# Adafruit_APDS9960_Proximity_Sensor.net
KiCad netlist of a schematic drawn in EAGLE
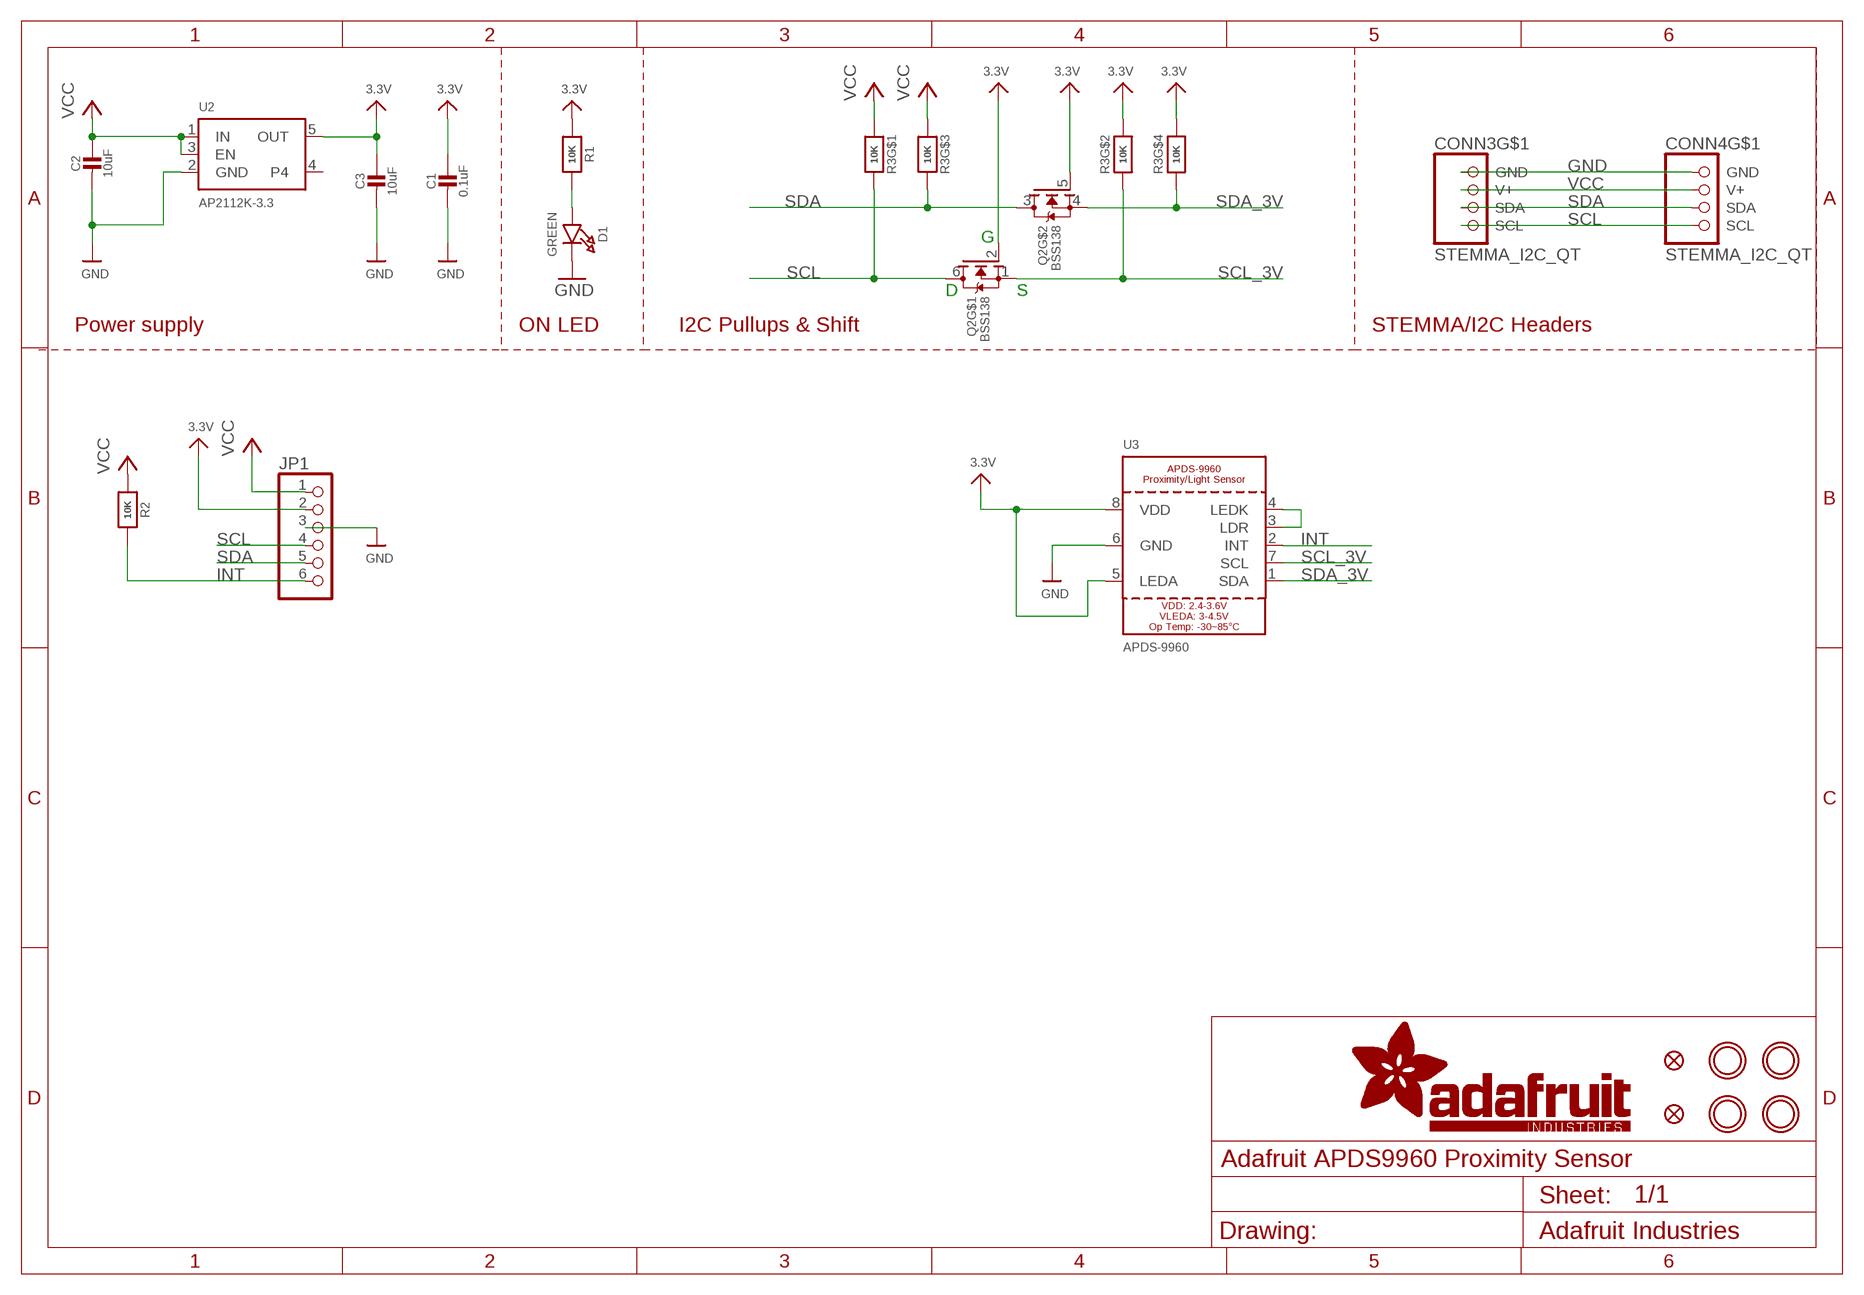
[diagram p0: schematic, sheet 1]

(export (version "E")
  (design (tool "Eeschema 10.0.6"))
  (components
    (comp (ref "C1")
      (value "0.1uF")
      (footprint "eagle-import:0603-NO")
      (libsource (lib "eagle-import") (part "CAP_CERAMIC0603_NO"))
    )
    (comp (ref "C2")
      (value "10uF")
      (footprint "eagle-import:0805-NO")
      (libsource (lib "eagle-import") (part "CAP_CERAMIC0805-NOOUTLINE"))
    )
    (comp (ref "C3")
      (value "10uF")
      (footprint "eagle-import:0805-NO")
      (libsource (lib "eagle-import") (part "CAP_CERAMIC0805-NOOUTLINE"))
    )
    (comp (ref "CONN3")
      (value "STEMMA_I2C_QT")
      (footprint "eagle-import:JST_SH4")
      (libsource (lib "eagle-import") (part "STEMMA_I2C_QT"))
    )
    (comp (ref "CONN4")
      (value "STEMMA_I2C_QT")
      (footprint "eagle-import:JST_SH4")
      (libsource (lib "eagle-import") (part "STEMMA_I2C_QT"))
    )
    (comp (ref "D1")
      (value "GREEN")
      (footprint "eagle-import:CHIPLED_0603_NOOUTLINE")
      (libsource (lib "eagle-import") (part "LED0603_NOOUTLINE"))
    )
    (comp (ref "FID3")
      (value "FIDUCIAL_1MM")
      (footprint "eagle-import:FIDUCIAL_1MM")
      (libsource (lib "eagle-import") (part "FIDUCIAL_1MM"))
    )
    (comp (ref "FID4")
      (value "FIDUCIAL_1MM")
      (footprint "eagle-import:FIDUCIAL_1MM")
      (libsource (lib "eagle-import") (part "FIDUCIAL_1MM"))
    )
    (comp (ref "JP1")
      (value "HEADER-1X670MIL")
      (footprint "eagle-import:1X06_ROUND_70")
      (libsource (lib "eagle-import") (part "HEADER-1X670MIL"))
    )
    (comp (ref "Q2")
      (value "BSS138")
      (footprint "eagle-import:SOT363")
      (libsource (lib "eagle-import") (part "MOSFET-N_DUAL"))
    )
    (comp (ref "R1")
      (value "10K")
      (footprint "eagle-import:0603-NO")
      (libsource (lib "eagle-import") (part "RESISTOR_0603_NOOUT"))
    )
    (comp (ref "R2")
      (value "10K")
      (footprint "eagle-import:0603-NO")
      (libsource (lib "eagle-import") (part "RESISTOR_0603_NOOUT"))
    )
    (comp (ref "R3")
      (value "10K")
      (footprint "eagle-import:RESPACK_4X0603")
      (libsource (lib "eagle-import") (part "RESISTOR_4PACK"))
    )
    (comp (ref "U$1")
      (value "MOUNTINGHOLE2.5")
      (footprint "eagle-import:MOUNTINGHOLE_2.5_PLATED")
      (libsource (lib "eagle-import") (part "MOUNTINGHOLE2.5"))
    )
    (comp (ref "U$17")
      (value "MOUNTINGHOLE2.5")
      (footprint "eagle-import:MOUNTINGHOLE_2.5_PLATED")
      (libsource (lib "eagle-import") (part "MOUNTINGHOLE2.5"))
    )
    (comp (ref "U$19")
      (value "MOUNTINGHOLE2.5")
      (footprint "eagle-import:MOUNTINGHOLE_2.5_PLATED")
      (libsource (lib "eagle-import") (part "MOUNTINGHOLE2.5"))
    )
    (comp (ref "U$21")
      (value "MOUNTINGHOLE2.5")
      (footprint "eagle-import:MOUNTINGHOLE_2.5_PLATED")
      (libsource (lib "eagle-import") (part "MOUNTINGHOLE2.5"))
    )
    (comp (ref "U2")
      (value "AP2112K-3.3")
      (footprint "eagle-import:SOT23-5")
      (libsource (lib "eagle-import") (part "VREG_SOT23-5"))
    )
    (comp (ref "U3")
      (value "APDS-9960")
      (footprint "eagle-import:APDS-9960")
      (libsource (lib "eagle-import") (part "APDS-9960"))
    )
  )
  (nets
    (net (code "1") (name "/INT") (class "Default")
      (node (ref "JP1") (pin "6") (pinfunction "6_6") (pintype "passive"))
      (node (ref "R2") (pin "2") (pinfunction "2_2") (pintype "passive"))
      (node (ref "U3") (pin "2") (pinfunction "INT_2") (pintype "output"))
    )
    (net (code "2") (name "/SCL") (class "Default")
      (node (ref "CONN3") (pin "4") (pinfunction "SCL_4") (pintype "passive"))
      (node (ref "CONN4") (pin "4") (pinfunction "SCL_4") (pintype "passive"))
      (node (ref "JP1") (pin "4") (pinfunction "4_4") (pintype "passive"))
      (node (ref "Q2") (pin "6") (pinfunction "D_6") (pintype "bidirectional"))
      (node (ref "R3") (pin "8") (pinfunction "2_8") (pintype "passive"))
    )
    (net (code "3") (name "/SCL_3V") (class "Default")
      (node (ref "Q2") (pin "1") (pinfunction "S_1") (pintype "bidirectional"))
      (node (ref "R3") (pin "7") (pinfunction "2_7") (pintype "passive"))
      (node (ref "U3") (pin "7") (pinfunction "SCL_7") (pintype "input"))
    )
    (net (code "4") (name "/SDA") (class "Default")
      (node (ref "CONN3") (pin "3") (pinfunction "SDA_3") (pintype "passive"))
      (node (ref "CONN4") (pin "3") (pinfunction "SDA_3") (pintype "passive"))
      (node (ref "JP1") (pin "5") (pinfunction "5_5") (pintype "passive"))
      (node (ref "Q2") (pin "3") (pinfunction "D_3") (pintype "bidirectional"))
      (node (ref "R3") (pin "6") (pinfunction "2_6") (pintype "passive"))
    )
    (net (code "5") (name "/SDA_3V") (class "Default")
      (node (ref "Q2") (pin "4") (pinfunction "S_4") (pintype "bidirectional"))
      (node (ref "R3") (pin "5") (pinfunction "2_5") (pintype "passive"))
      (node (ref "U3") (pin "1") (pinfunction "SDA_1") (pintype "bidirectional"))
    )
    (net (code "6") (name "3.3V") (class "Default")
      (node (ref "C1") (pin "1") (pinfunction "1_1") (pintype "passive"))
      (node (ref "C3") (pin "1") (pinfunction "1_1") (pintype "passive"))
      (node (ref "JP1") (pin "2") (pinfunction "2_2") (pintype "passive"))
      (node (ref "Q2") (pin "2") (pinfunction "G_2") (pintype "bidirectional"))
      (node (ref "Q2") (pin "5") (pinfunction "G_5") (pintype "bidirectional"))
      (node (ref "R1") (pin "1") (pinfunction "1_1") (pintype "passive"))
      (node (ref "R3") (pin "2") (pinfunction "1_2") (pintype "passive"))
      (node (ref "R3") (pin "4") (pinfunction "1_4") (pintype "passive"))
      (node (ref "U2") (pin "5") (pinfunction "OUT_5") (pintype "power_in"))
      (node (ref "U3") (pin "5") (pinfunction "LEDA_5") (pintype "power_in"))
      (node (ref "U3") (pin "8") (pinfunction "VDD_8") (pintype "power_in"))
    )
    (net (code "7") (name "GND") (class "Default")
      (node (ref "C1") (pin "2") (pinfunction "2_2") (pintype "passive"))
      (node (ref "C2") (pin "2") (pinfunction "2_2") (pintype "passive"))
      (node (ref "C3") (pin "2") (pinfunction "2_2") (pintype "passive"))
      (node (ref "CONN3") (pin "1") (pinfunction "GND_1") (pintype "passive"))
      (node (ref "CONN4") (pin "1") (pinfunction "GND_1") (pintype "passive"))
      (node (ref "D1") (pin "C") (pinfunction "C_C") (pintype "passive"))
      (node (ref "JP1") (pin "3") (pinfunction "3_3") (pintype "passive"))
      (node (ref "U2") (pin "2") (pinfunction "GND_2") (pintype "power_in"))
      (node (ref "U3") (pin "6") (pinfunction "GND_6") (pintype "power_in"))
    )
    (net (code "8") (name "Net-(D1-PadA)") (class "Default")
      (node (ref "D1") (pin "A") (pinfunction "A_A") (pintype "passive"))
      (node (ref "R1") (pin "2") (pinfunction "2_2") (pintype "passive"))
    )
    (net (code "9") (name "Net-(U3-LDR)") (class "Default")
      (node (ref "U3") (pin "3") (pinfunction "LDR_3") (pintype "bidirectional"))
      (node (ref "U3") (pin "4") (pinfunction "LEDK_4") (pintype "bidirectional"))
    )
    (net (code "10") (name "VCC") (class "Default")
      (node (ref "C2") (pin "1") (pinfunction "1_1") (pintype "passive"))
      (node (ref "CONN3") (pin "2") (pinfunction "V+_2") (pintype "passive"))
      (node (ref "CONN4") (pin "2") (pinfunction "V+_2") (pintype "passive"))
      (node (ref "JP1") (pin "1") (pinfunction "1_1") (pintype "passive"))
      (node (ref "R2") (pin "1") (pinfunction "1_1") (pintype "passive"))
      (node (ref "R3") (pin "1") (pinfunction "1_1") (pintype "passive"))
      (node (ref "R3") (pin "3") (pinfunction "1_3") (pintype "passive"))
      (node (ref "U2") (pin "1") (pinfunction "IN_1") (pintype "power_in"))
      (node (ref "U2") (pin "3") (pinfunction "EN_3") (pintype "input"))
    )
    (net (code "11") (name "unconnected-(U2-P4-Pad4)") (class "Default")
      (node (ref "U2") (pin "4") (pinfunction "P4_4") (pintype "bidirectional"))
    )
  )
)
